# A_E_K.net
KiCad netlist of a schematic drawn in EAGLE
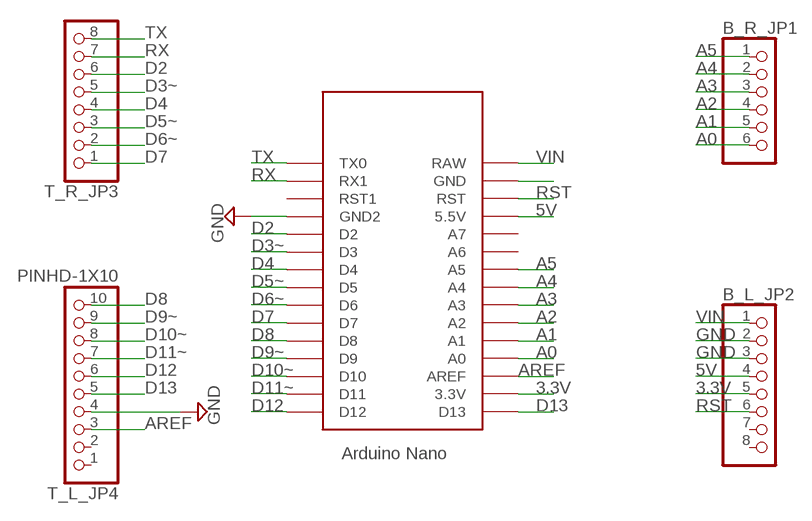
[diagram p0: schematic, sheet 1]
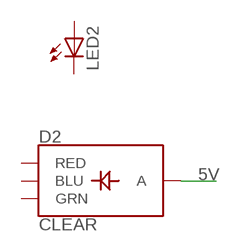
[diagram p1: schematic, sheet 2]

(export (version "E")
  (design (tool "Eeschema 10.0.6"))
  (components
    (comp (ref "D2")
      (value "CLEAR")
      (footprint "eagle-import:LED-RGB-THRU")
      (libsource (lib "eagle-import") (part "LED-RGB-CACLEAR"))
    )
    (comp (ref "LED2")
      (value "LED5MM")
      (footprint "eagle-import:LED5MM")
      (libsource (lib "eagle-import") (part "LED5MM"))
    )
    (comp (ref "B_L_JP2")
      (value "PINHD-1X8BIG")
      (footprint "eagle-import:1X08-BIG")
      (libsource (lib "eagle-import") (part "PINHD-1X8BIG"))
    )
    (comp (ref "B_R_JP1")
      (value "PINHD-1X6B")
      (footprint "eagle-import:1X06-BIG")
      (libsource (lib "eagle-import") (part "PINHD-1X6B"))
    )
    (comp (ref "T_L_JP4")
      (value "PINHD-1X10")
      (footprint "eagle-import:1X10-BIG")
      (libsource (lib "eagle-import") (part "PINHD-1X10"))
    )
    (comp (ref "T_R_JP3")
      (value "PINHD-1X8BIG")
      (footprint "eagle-import:1X08-BIG")
      (libsource (lib "eagle-import") (part "PINHD-1X8BIG"))
    )
    (comp (ref "U$1")
      (value "NANO")
      (footprint "eagle-import:NANO")
      (libsource (lib "eagle-import") (part "NANO"))
    )
  )
  (nets
    (net (code "1") (name "3.3V") (class "Default")
      (node (ref "B_L_JP2") (pin "5") (pinfunction "5_5") (pintype "passive"))
      (node (ref "U$1") (pin "3.3V") (pinfunction "3.3V_3.3V") (pintype "bidirectional"))
    )
    (net (code "2") (name "5V") (class "Default")
      (node (ref "B_L_JP2") (pin "4") (pinfunction "4_4") (pintype "passive"))
      (node (ref "D2") (pin "2") (pinfunction "A_2") (pintype "bidirectional"))
      (node (ref "U$1") (pin "5V") (pinfunction "5.5V_5V") (pintype "bidirectional"))
    )
    (net (code "3") (name "A0") (class "Default")
      (node (ref "B_R_JP1") (pin "6") (pinfunction "6_6") (pintype "passive"))
      (node (ref "U$1") (pin "A0") (pinfunction "A0_A0") (pintype "bidirectional"))
    )
    (net (code "4") (name "A1") (class "Default")
      (node (ref "B_R_JP1") (pin "5") (pinfunction "5_5") (pintype "passive"))
      (node (ref "U$1") (pin "A1") (pinfunction "A1_A1") (pintype "bidirectional"))
    )
    (net (code "5") (name "A2") (class "Default")
      (node (ref "B_R_JP1") (pin "4") (pinfunction "4_4") (pintype "passive"))
      (node (ref "U$1") (pin "A2") (pinfunction "A2_A2") (pintype "bidirectional"))
    )
    (net (code "6") (name "A3") (class "Default")
      (node (ref "B_R_JP1") (pin "3") (pinfunction "3_3") (pintype "passive"))
      (node (ref "U$1") (pin "A3") (pinfunction "A3_A3") (pintype "bidirectional"))
    )
    (net (code "7") (name "A4") (class "Default")
      (node (ref "B_R_JP1") (pin "2") (pinfunction "2_2") (pintype "passive"))
      (node (ref "U$1") (pin "A4") (pinfunction "A4_A4") (pintype "bidirectional"))
    )
    (net (code "8") (name "A5") (class "Default")
      (node (ref "B_R_JP1") (pin "1") (pinfunction "1_1") (pintype "passive"))
      (node (ref "U$1") (pin "A5") (pinfunction "A5_A5") (pintype "bidirectional"))
    )
    (net (code "9") (name "AREF") (class "Default")
      (node (ref "T_L_JP4") (pin "3") (pinfunction "3_3") (pintype "passive"))
      (node (ref "U$1") (pin "AREF") (pinfunction "AREF_AREF") (pintype "bidirectional"))
    )
    (net (code "10") (name "D2") (class "Default")
      (node (ref "T_R_JP3") (pin "6") (pinfunction "6_6") (pintype "passive"))
      (node (ref "U$1") (pin "D2") (pinfunction "D2_D2") (pintype "bidirectional"))
    )
    (net (code "11") (name "D3~{}") (class "Default")
      (node (ref "T_R_JP3") (pin "5") (pinfunction "5_5") (pintype "passive"))
      (node (ref "U$1") (pin "D3") (pinfunction "D3_D3") (pintype "bidirectional"))
    )
    (net (code "12") (name "D4") (class "Default")
      (node (ref "T_R_JP3") (pin "4") (pinfunction "4_4") (pintype "passive"))
      (node (ref "U$1") (pin "D4") (pinfunction "D4_D4") (pintype "bidirectional"))
    )
    (net (code "13") (name "D5~{}") (class "Default")
      (node (ref "T_R_JP3") (pin "3") (pinfunction "3_3") (pintype "passive"))
      (node (ref "U$1") (pin "D5") (pinfunction "D5_D5") (pintype "bidirectional"))
    )
    (net (code "14") (name "D6~{}") (class "Default")
      (node (ref "T_R_JP3") (pin "2") (pinfunction "2_2") (pintype "passive"))
      (node (ref "U$1") (pin "D6") (pinfunction "D6_D6") (pintype "bidirectional"))
    )
    (net (code "15") (name "D7") (class "Default")
      (node (ref "T_R_JP3") (pin "1") (pinfunction "1_1") (pintype "passive"))
      (node (ref "U$1") (pin "D7") (pinfunction "D7_D7") (pintype "bidirectional"))
    )
    (net (code "16") (name "D8") (class "Default")
      (node (ref "T_L_JP4") (pin "10") (pinfunction "10_10") (pintype "passive"))
      (node (ref "U$1") (pin "D8") (pinfunction "D8_D8") (pintype "bidirectional"))
    )
    (net (code "17") (name "D9~{}") (class "Default")
      (node (ref "T_L_JP4") (pin "9") (pinfunction "9_9") (pintype "passive"))
      (node (ref "U$1") (pin "D9") (pinfunction "D9_D9") (pintype "bidirectional"))
    )
    (net (code "18") (name "D10~{}") (class "Default")
      (node (ref "T_L_JP4") (pin "8") (pinfunction "8_8") (pintype "passive"))
      (node (ref "U$1") (pin "D10") (pinfunction "D10_D10") (pintype "bidirectional"))
    )
    (net (code "19") (name "D11~{}") (class "Default")
      (node (ref "T_L_JP4") (pin "7") (pinfunction "7_7") (pintype "passive"))
      (node (ref "U$1") (pin "D11") (pinfunction "D11_D11") (pintype "bidirectional"))
    )
    (net (code "20") (name "D12") (class "Default")
      (node (ref "T_L_JP4") (pin "6") (pinfunction "6_6") (pintype "passive"))
      (node (ref "U$1") (pin "D12") (pinfunction "D12_D12") (pintype "bidirectional"))
    )
    (net (code "21") (name "D13") (class "Default")
      (node (ref "T_L_JP4") (pin "5") (pinfunction "5_5") (pintype "passive"))
      (node (ref "U$1") (pin "D13") (pinfunction "D13_D13") (pintype "bidirectional"))
    )
    (net (code "22") (name "GND") (class "Default")
      (node (ref "B_L_JP2") (pin "2") (pinfunction "2_2") (pintype "passive"))
      (node (ref "B_L_JP2") (pin "3") (pinfunction "3_3") (pintype "passive"))
      (node (ref "T_L_JP4") (pin "4") (pinfunction "4_4") (pintype "passive"))
      (node (ref "U$1") (pin "GND1") (pinfunction "GND2_GND1") (pintype "bidirectional"))
    )
    (net (code "23") (name "RST") (class "Default")
      (node (ref "B_L_JP2") (pin "6") (pinfunction "6_6") (pintype "passive"))
      (node (ref "U$1") (pin "RST") (pinfunction "RST_RST") (pintype "bidirectional"))
    )
    (net (code "24") (name "RX") (class "Default")
      (node (ref "T_R_JP3") (pin "7") (pinfunction "7_7") (pintype "passive"))
      (node (ref "U$1") (pin "RX1") (pinfunction "RX1_RX1") (pintype "bidirectional"))
    )
    (net (code "25") (name "TX") (class "Default")
      (node (ref "T_R_JP3") (pin "8") (pinfunction "8_8") (pintype "passive"))
      (node (ref "U$1") (pin "TX0") (pinfunction "TX0_TX0") (pintype "bidirectional"))
    )
    (net (code "26") (name "VIN") (class "Default")
      (node (ref "B_L_JP2") (pin "1") (pinfunction "1_1") (pintype "passive"))
      (node (ref "U$1") (pin "RAW") (pinfunction "RAW_RAW") (pintype "bidirectional"))
    )
    (net (code "27") (name "unconnected-(B_L_JP2-Pad7)") (class "Default")
      (node (ref "B_L_JP2") (pin "7") (pinfunction "7_7") (pintype "passive"))
    )
    (net (code "28") (name "unconnected-(B_L_JP2-Pad8)") (class "Default")
      (node (ref "B_L_JP2") (pin "8") (pinfunction "8_8") (pintype "passive"))
    )
    (net (code "29") (name "unconnected-(D2-BLU-Pad4)") (class "Default")
      (node (ref "D2") (pin "4") (pinfunction "BLU_4") (pintype "bidirectional"))
    )
    (net (code "30") (name "unconnected-(D2-GRN-Pad3)") (class "Default")
      (node (ref "D2") (pin "3") (pinfunction "GRN_3") (pintype "bidirectional"))
    )
    (net (code "31") (name "unconnected-(D2-RED-Pad1)") (class "Default")
      (node (ref "D2") (pin "1") (pinfunction "RED_1") (pintype "bidirectional"))
    )
    (net (code "32") (name "unconnected-(LED2-C-PadK)") (class "Default")
      (node (ref "LED2") (pin "K") (pinfunction "C_K") (pintype "passive"))
    )
    (net (code "33") (name "unconnected-(LED2-PadA)") (class "Default")
      (node (ref "LED2") (pin "A") (pinfunction "A_A") (pintype "passive"))
    )
    (net (code "34") (name "unconnected-(T_L_JP4-Pad1)") (class "Default")
      (node (ref "T_L_JP4") (pin "1") (pinfunction "1_1") (pintype "passive"))
    )
    (net (code "35") (name "unconnected-(T_L_JP4-Pad2)") (class "Default")
      (node (ref "T_L_JP4") (pin "2") (pinfunction "2_2") (pintype "passive"))
    )
    (net (code "36") (name "unconnected-(U$1-PadA6)") (class "Default")
      (node (ref "U$1") (pin "A6") (pinfunction "A6_A6") (pintype "bidirectional"))
    )
    (net (code "37") (name "unconnected-(U$1-PadA7)") (class "Default")
      (node (ref "U$1") (pin "A7") (pinfunction "A7_A7") (pintype "bidirectional"))
    )
    (net (code "38") (name "unconnected-(U$1-PadGND)") (class "Default")
      (node (ref "U$1") (pin "GND") (pinfunction "GND_GND") (pintype "bidirectional"))
    )
    (net (code "39") (name "unconnected-(U$1-PadICSP1)") (class "Default")
      (node (ref "U$1") (pin "ICSP1") (pinfunction "ICSP1_ICSP1") (pintype "bidirectional"))
    )
    (net (code "40") (name "unconnected-(U$1-PadICSP2)") (class "Default")
      (node (ref "U$1") (pin "ICSP2") (pinfunction "ICSP2_ICSP2") (pintype "bidirectional"))
    )
    (net (code "41") (name "unconnected-(U$1-PadICSP3)") (class "Default")
      (node (ref "U$1") (pin "ICSP3") (pinfunction "ICSP3_ICSP3") (pintype "bidirectional"))
    )
    (net (code "42") (name "unconnected-(U$1-PadICSP4)") (class "Default")
      (node (ref "U$1") (pin "ICSP4") (pinfunction "ICSP4_ICSP4") (pintype "bidirectional"))
    )
    (net (code "43") (name "unconnected-(U$1-PadICSP5)") (class "Default")
      (node (ref "U$1") (pin "ICSP5") (pinfunction "ICSP5_ICSP5") (pintype "bidirectional"))
    )
    (net (code "44") (name "unconnected-(U$1-PadICSP6)") (class "Default")
      (node (ref "U$1") (pin "ICSP6") (pinfunction "ICSP6_ICSP6") (pintype "bidirectional"))
    )
    (net (code "45") (name "unconnected-(U$1-PadRST1)") (class "Default")
      (node (ref "U$1") (pin "RST1") (pinfunction "RST1_RST1") (pintype "bidirectional"))
    )
  )
)
